# NX1117C33Z.net
KiCad netlist of a schematic drawn in Altium Designer
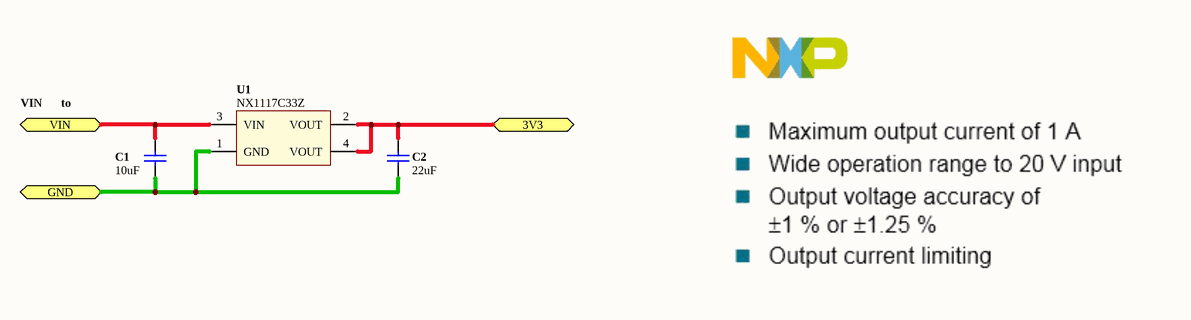
[diagram p0: NX1117C33Z.SchDoc]

(export (version "E")
  (design (tool "Eeschema 10.0.6"))
  (components
    (comp (ref "C1")
      (value "10uF")
      (footprint "CAPC0805(2012)100_N")
      (description "CAP 10uF 10V ±20% 0805 (2012 Metric) Thickness 1mm SMD")
      (fields (field (name "TOLERANCE") "±20%") (field (name "Comment") "CAP 10uF 10V 0805(2012)"))
      (libsource (lib "Altium Content Vault") (part "CMP-1036-04925-1"))
    )
    (comp (ref "C2")
      (value "22uF")
      (footprint "CAPC1206(3216)100_L")
      (description "CAP 22uF 6.3V ±20% 1206 (3216 Metric) Thickness 1mm SMD")
      (fields (field (name "TOLERANCE") "±20%") (field (name "Comment") "CAP 22uF 6.3V 1206(3216)"))
      (libsource (lib "Altium Content Vault") (part "CMP-1037-04987-1"))
    )
    (comp (ref "U1")
      (value "NX1117C33Z")
      (footprint "NXP-SOT223")
      (description "Low-dropout linear regulator, 3.3V Output, SOT223")
      (libsource (lib "Altium Content Vault") (part "CMP-5296-00001-1"))
    )
  )
  (nets
    (net (code "1") (name "/3V3") (class "Default")
      (node (ref "C2") (pin "2") (pinfunction "2_2") (pintype "passive"))
      (node (ref "U1") (pin "2") (pinfunction "VOUT_2") (pintype "power_in"))
      (node (ref "U1") (pin "4") (pinfunction "VOUT_4") (pintype "power_in"))
    )
    (net (code "2") (name "/GND") (class "Default")
      (node (ref "C1") (pin "1") (pinfunction "1_1") (pintype "passive"))
      (node (ref "C2") (pin "1") (pinfunction "1_1") (pintype "passive"))
      (node (ref "U1") (pin "1") (pinfunction "GND_1") (pintype "power_in"))
    )
    (net (code "3") (name "/VIN") (class "Default")
      (node (ref "C1") (pin "2") (pinfunction "2_2") (pintype "passive"))
      (node (ref "U1") (pin "3") (pinfunction "VIN_3") (pintype "power_in"))
    )
  )
)
